# Communication.net
KiCad netlist of a schematic drawn in Altium Designer
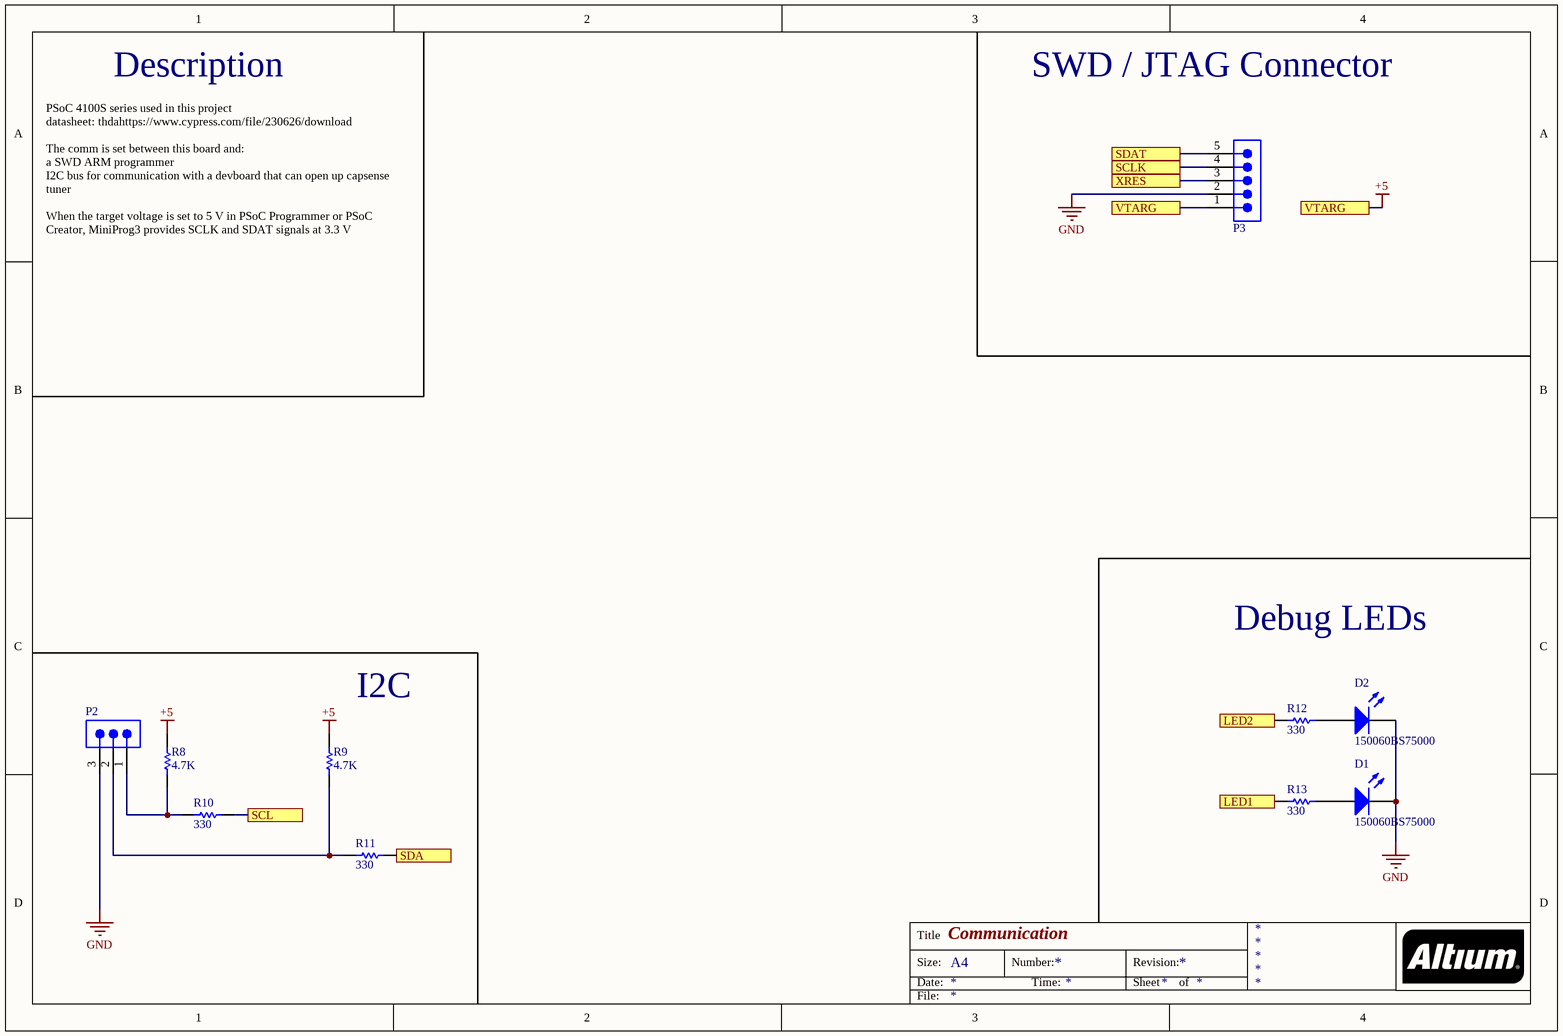
[diagram p0: Communication.SchDoc]

(export (version "E")
  (design (tool "Eeschema 10.0.6"))
  (components
    (comp (ref "D1")
      (value "150060BS75000")
      (footprint "0603_A")
      (description "SMD mono-color Chip LED, WL-SMCW, Blue")
      (fields (field (name "MANUFACTURER") "Wuerth Elektronik"))
      (libsource (lib "Altium Content Vault") (part "WE-LED_K1A2-2"))
    )
    (comp (ref "D2")
      (value "150060BS75000")
      (footprint "0603_A")
      (description "SMD mono-color Chip LED, WL-SMCW, Blue")
      (fields (field (name "MANUFACTURER") "Wuerth Elektronik"))
      (libsource (lib "Altium Content Vault") (part "WE-LED_K1A2-2"))
    )
    (comp (ref "P2")
      (value "TSW-103-07-F-S")
      (footprint "SMTC-TSW-103-07-X-S")
      (description "0.025\" SQ Post Header, Through-hole, Vertical, -55 to 125 degC, 2.54 mm Pitch, 3-Pin, Male, RoHS")
      (fields (field (name "MANUFACTURER") "Samtec"))
      (libsource (lib "Altium Content Vault") (part "SMTC-TSW-103-X-X-S-X"))
    )
    (comp (ref "P3")
      (value "MTLW-105-05-L-S-190")
      (footprint "SMTC-MTLW-105-05-X-S-190")
      (fields (field (name "MANUFACTURER") "Samtec"))
      (libsource (lib "Altium Content Vault") (part "SMTC-MTLW-105-05-X-S-190"))
    )
    (comp (ref "R8")
      (value "4.7K")
      (footprint "RESC1608X55X25ML10T15")
      (fields (field (name "TOLERANCE") "5%") (field (name "MANUFACTURER") "Yageo"))
      (libsource (lib "Altium Content Vault") (part "RES-2"))
    )
    (comp (ref "R9")
      (value "4.7K")
      (footprint "RESC1608X55X25ML10T15")
      (fields (field (name "TOLERANCE") "5%") (field (name "MANUFACTURER") "Yageo"))
      (libsource (lib "Altium Content Vault") (part "RES-2"))
    )
    (comp (ref "R10")
      (value "330")
      (footprint "RESC0603(1608)_L")
      (description "330R 0.1W 5% 0603 (1608 Metric)  SMD")
      (fields (field (name "TOLERANCE") "5 %") (field (name "POWER") "0.1 W"))
      (libsource (lib "Altium Content Vault") (part "RES"))
    )
    (comp (ref "R11")
      (value "330")
      (footprint "RESC0603(1608)_L")
      (description "330R 0.1W 5% 0603 (1608 Metric)  SMD")
      (fields (field (name "TOLERANCE") "5 %") (field (name "POWER") "0.1 W"))
      (libsource (lib "Altium Content Vault") (part "RES"))
    )
    (comp (ref "R12")
      (value "330")
      (footprint "RESC0603(1608)_L")
      (description "330R 0.1W 5% 0603 (1608 Metric)  SMD")
      (fields (field (name "TOLERANCE") "5 %") (field (name "POWER") "0.1 W"))
      (libsource (lib "Altium Content Vault") (part "RES"))
    )
    (comp (ref "R13")
      (value "330")
      (footprint "RESC0603(1608)_L")
      (description "330R 0.1W 5% 0603 (1608 Metric)  SMD")
      (fields (field (name "TOLERANCE") "5 %") (field (name "POWER") "0.1 W"))
      (libsource (lib "Altium Content Vault") (part "RES"))
    )
  )
  (nets
    (net (code "1") (name "+5") (class "Default")
      (node (ref "P3") (pin "1") (pinfunction "1_1") (pintype "passive"))
      (node (ref "R8") (pin "2") (pinfunction "2_2") (pintype "passive"))
      (node (ref "R9") (pin "2") (pinfunction "2_2") (pintype "passive"))
    )
    (net (code "2") (name "/LED1") (class "Default")
      (node (ref "R13") (pin "1") (pinfunction "1_1") (pintype "passive"))
    )
    (net (code "3") (name "/LED2") (class "Default")
      (node (ref "R12") (pin "1") (pinfunction "1_1") (pintype "passive"))
    )
    (net (code "4") (name "/SCL") (class "Default")
      (node (ref "R10") (pin "2") (pinfunction "2_2") (pintype "passive"))
    )
    (net (code "5") (name "/SCLK") (class "Default")
      (node (ref "P3") (pin "4") (pinfunction "4_4") (pintype "passive"))
    )
    (net (code "6") (name "/SDA") (class "Default")
      (node (ref "R11") (pin "2") (pinfunction "2_2") (pintype "passive"))
    )
    (net (code "7") (name "/SDAT") (class "Default")
      (node (ref "P3") (pin "5") (pinfunction "5_5") (pintype "passive"))
    )
    (net (code "8") (name "/XRES") (class "Default")
      (node (ref "P3") (pin "3") (pinfunction "3_3") (pintype "passive"))
    )
    (net (code "9") (name "GND") (class "Default")
      (node (ref "D1") (pin "1") (pinfunction "K_1") (pintype "passive"))
      (node (ref "D2") (pin "1") (pinfunction "K_1") (pintype "passive"))
      (node (ref "P2") (pin "3") (pinfunction "3_3") (pintype "passive"))
      (node (ref "P3") (pin "2") (pinfunction "2_2") (pintype "passive"))
    )
    (net (code "10") (name "Net-(D1-A)") (class "Default")
      (node (ref "D1") (pin "2") (pinfunction "A_2") (pintype "passive"))
      (node (ref "R13") (pin "2") (pinfunction "2_2") (pintype "passive"))
    )
    (net (code "11") (name "Net-(D2-A)") (class "Default")
      (node (ref "D2") (pin "2") (pinfunction "A_2") (pintype "passive"))
      (node (ref "R12") (pin "2") (pinfunction "2_2") (pintype "passive"))
    )
    (net (code "12") (name "Net-(P2-Pad1)") (class "Default")
      (node (ref "P2") (pin "1") (pinfunction "1_1") (pintype "passive"))
      (node (ref "R10") (pin "1") (pinfunction "1_1") (pintype "passive"))
      (node (ref "R8") (pin "1") (pinfunction "1_1") (pintype "passive"))
    )
    (net (code "13") (name "Net-(P2-Pad2)") (class "Default")
      (node (ref "P2") (pin "2") (pinfunction "2_2") (pintype "passive"))
      (node (ref "R11") (pin "1") (pinfunction "1_1") (pintype "passive"))
      (node (ref "R9") (pin "1") (pinfunction "1_1") (pintype "passive"))
    )
  )
)
